# tempSens_Photon.net
KiCad netlist of a schematic drawn in EAGLE
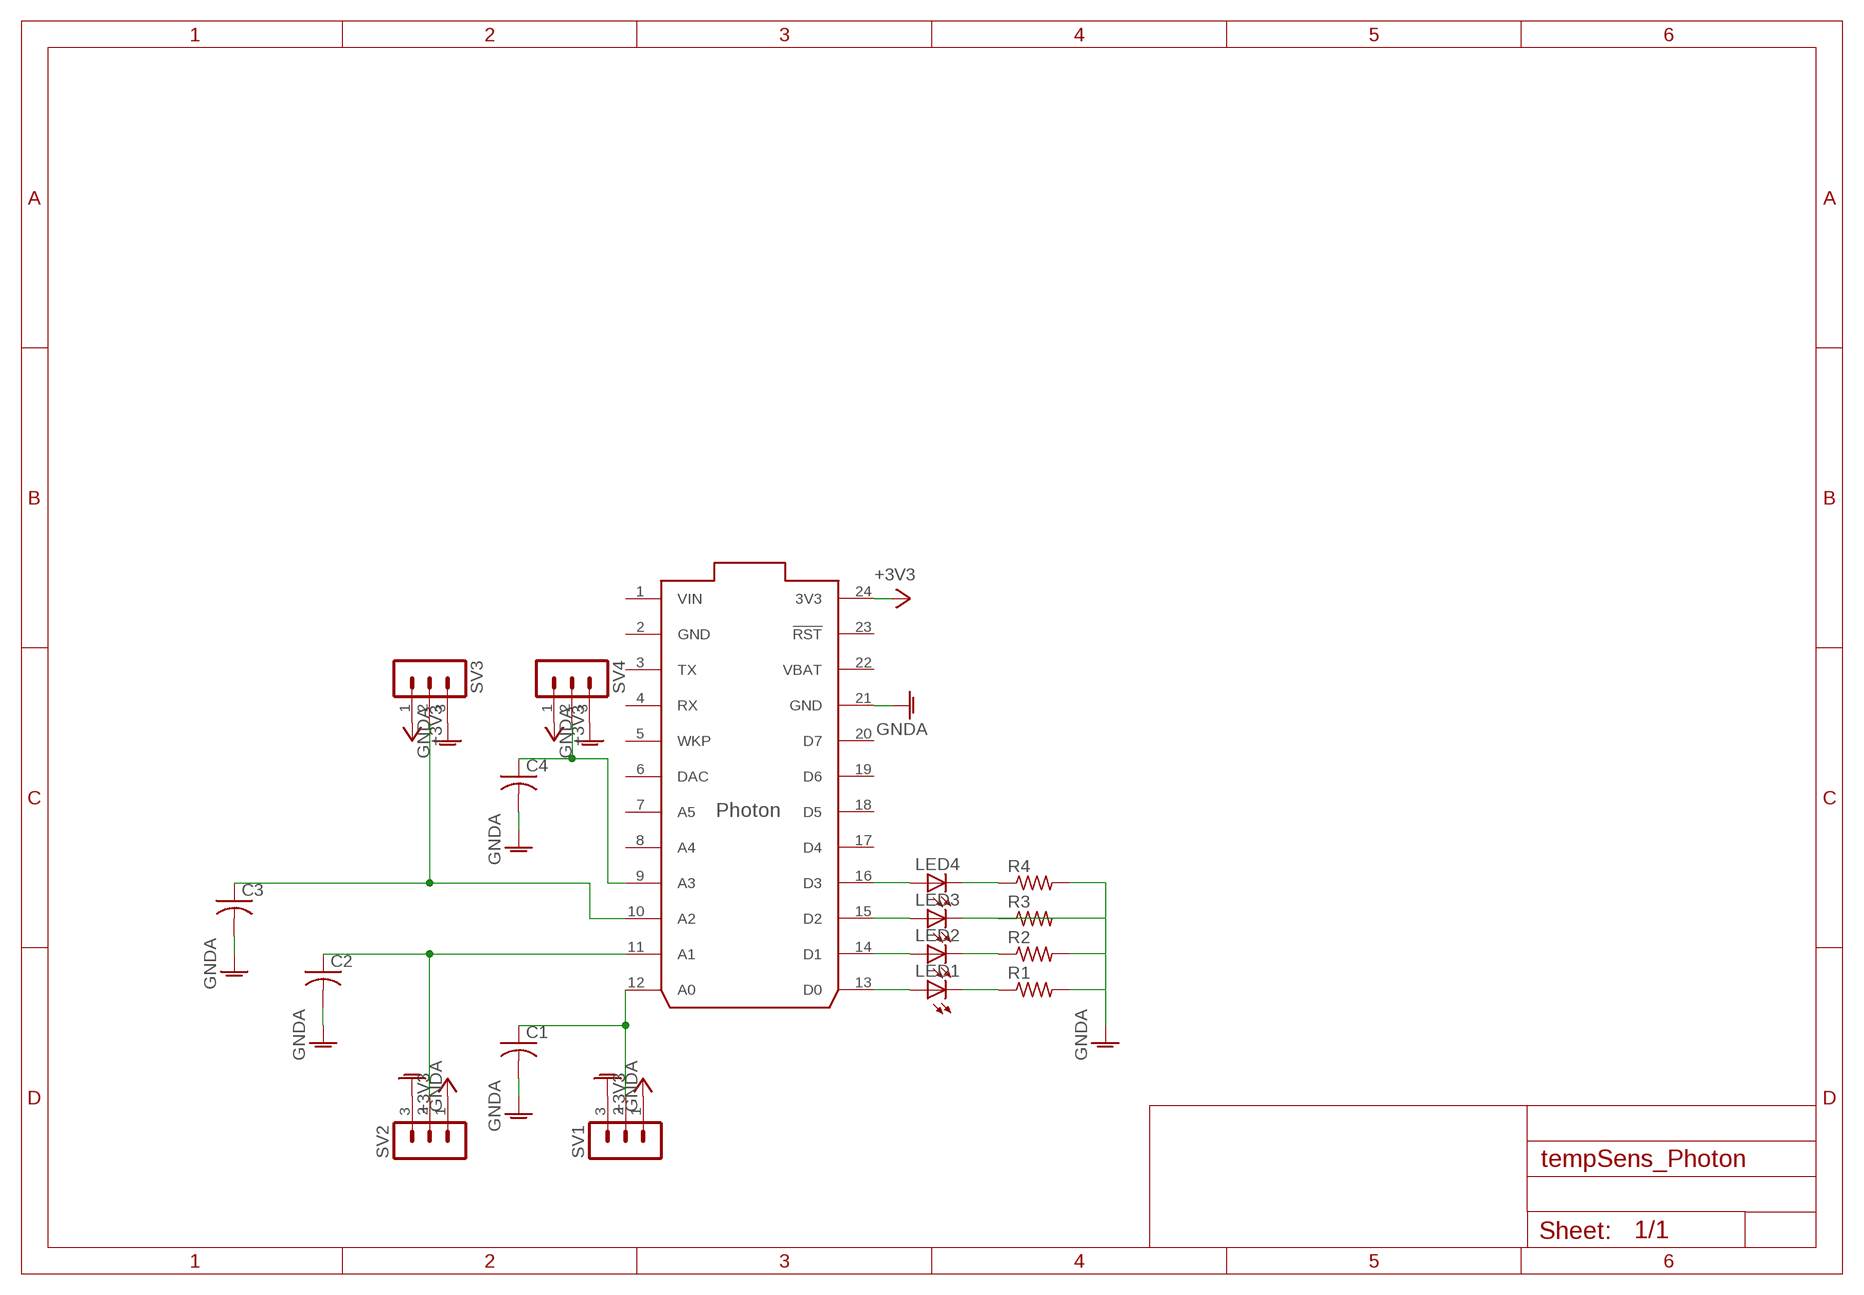
[diagram p0: schematic, sheet 1]

(export (version "E")
  (design (tool "Eeschema 10.0.6"))
  (components
    (comp (ref "C1")
      (value "C-USC0805")
      (footprint "eagle-import:C0805")
      (libsource (lib "eagle-import") (part "C-USC0805"))
    )
    (comp (ref "C2")
      (value "C-USC0805")
      (footprint "eagle-import:C0805")
      (libsource (lib "eagle-import") (part "C-USC0805"))
    )
    (comp (ref "C3")
      (value "C-USC0805")
      (footprint "eagle-import:C0805")
      (libsource (lib "eagle-import") (part "C-USC0805"))
    )
    (comp (ref "C4")
      (value "C-USC0805")
      (footprint "eagle-import:C0805")
      (libsource (lib "eagle-import") (part "C-USC0805"))
    )
    (comp (ref "LED1")
      (value "LEDCHIPLED_0805")
      (footprint "eagle-import:CHIPLED_0805")
      (libsource (lib "eagle-import") (part "LEDCHIPLED_0805"))
    )
    (comp (ref "LED2")
      (value "LEDCHIPLED_0805")
      (footprint "eagle-import:CHIPLED_0805")
      (libsource (lib "eagle-import") (part "LEDCHIPLED_0805"))
    )
    (comp (ref "LED3")
      (value "LEDCHIPLED_0805")
      (footprint "eagle-import:CHIPLED_0805")
      (libsource (lib "eagle-import") (part "LEDCHIPLED_0805"))
    )
    (comp (ref "LED4")
      (value "LEDCHIPLED_0805")
      (footprint "eagle-import:CHIPLED_0805")
      (libsource (lib "eagle-import") (part "LEDCHIPLED_0805"))
    )
    (comp (ref "R1")
      (value "R-US_R0805")
      (footprint "eagle-import:R0805")
      (libsource (lib "eagle-import") (part "R-US_R0805"))
    )
    (comp (ref "R2")
      (value "R-US_R0805")
      (footprint "eagle-import:R0805")
      (libsource (lib "eagle-import") (part "R-US_R0805"))
    )
    (comp (ref "R3")
      (value "R-US_R0805")
      (footprint "eagle-import:R0805")
      (libsource (lib "eagle-import") (part "R-US_R0805"))
    )
    (comp (ref "R4")
      (value "R-US_R0805")
      (footprint "eagle-import:R0805")
      (libsource (lib "eagle-import") (part "R-US_R0805"))
    )
    (comp (ref "SV1")
      (value "CONN3PIN")
      (footprint "eagle-import:MA03-1")
      (libsource (lib "eagle-import") (part "CONN3PIN"))
    )
    (comp (ref "SV2")
      (value "CONN3PIN")
      (footprint "eagle-import:MA03-1")
      (libsource (lib "eagle-import") (part "CONN3PIN"))
    )
    (comp (ref "SV3")
      (value "CONN3PIN")
      (footprint "eagle-import:MA03-1")
      (libsource (lib "eagle-import") (part "CONN3PIN"))
    )
    (comp (ref "SV4")
      (value "CONN3PIN")
      (footprint "eagle-import:MA03-1")
      (libsource (lib "eagle-import") (part "CONN3PIN"))
    )
    (comp (ref "U$1")
      (value "PHOTON_SMD")
      (footprint "eagle-import:PHOTON_SMD")
      (libsource (lib "eagle-import") (part "PHOTON_SMD"))
    )
  )
  (nets
    (net (code "1") (name "+3V3") (class "Default")
      (node (ref "SV1") (pin "1") (pinfunction "1_1") (pintype "passive"))
      (node (ref "SV2") (pin "1") (pinfunction "1_1") (pintype "passive"))
      (node (ref "SV3") (pin "1") (pinfunction "1_1") (pintype "passive"))
      (node (ref "SV4") (pin "1") (pinfunction "1_1") (pintype "passive"))
      (node (ref "U$1") (pin "24") (pinfunction "3V3_24") (pintype "power_in"))
    )
    (net (code "2") (name "/GND") (class "Default")
      (node (ref "U$1") (pin "2") (pinfunction "GND_2") (pintype "power_in"))
    )
    (net (code "3") (name "/VBAT") (class "Default")
      (node (ref "U$1") (pin "22") (pinfunction "VBAT_22") (pintype "power_in"))
    )
    (net (code "4") (name "/VIN") (class "Default")
      (node (ref "U$1") (pin "1") (pinfunction "VIN_1") (pintype "power_in"))
    )
    (net (code "5") (name "GNDA") (class "Default")
      (node (ref "C1") (pin "2") (pinfunction "2_2") (pintype "passive"))
      (node (ref "C2") (pin "2") (pinfunction "2_2") (pintype "passive"))
      (node (ref "C3") (pin "2") (pinfunction "2_2") (pintype "passive"))
      (node (ref "C4") (pin "2") (pinfunction "2_2") (pintype "passive"))
      (node (ref "R1") (pin "2") (pinfunction "2_2") (pintype "passive"))
      (node (ref "R2") (pin "2") (pinfunction "2_2") (pintype "passive"))
      (node (ref "R3") (pin "1") (pinfunction "1_1") (pintype "passive"))
      (node (ref "R4") (pin "2") (pinfunction "2_2") (pintype "passive"))
      (node (ref "SV1") (pin "3") (pinfunction "3_3") (pintype "passive"))
      (node (ref "SV2") (pin "3") (pinfunction "3_3") (pintype "passive"))
      (node (ref "SV3") (pin "3") (pinfunction "3_3") (pintype "passive"))
      (node (ref "SV4") (pin "3") (pinfunction "3_3") (pintype "passive"))
      (node (ref "U$1") (pin "21") (pinfunction "GND_21") (pintype "power_in"))
    )
    (net (code "6") (name "Net-(LED1-PadC)") (class "Default")
      (node (ref "LED1") (pin "C") (pinfunction "C_C") (pintype "passive"))
      (node (ref "R1") (pin "1") (pinfunction "1_1") (pintype "passive"))
    )
    (net (code "7") (name "Net-(LED2-PadC)") (class "Default")
      (node (ref "LED2") (pin "C") (pinfunction "C_C") (pintype "passive"))
      (node (ref "R2") (pin "1") (pinfunction "1_1") (pintype "passive"))
    )
    (net (code "8") (name "Net-(LED3-PadC)") (class "Default")
      (node (ref "LED3") (pin "C") (pinfunction "C_C") (pintype "passive"))
      (node (ref "R3") (pin "2") (pinfunction "2_2") (pintype "passive"))
    )
    (net (code "9") (name "Net-(LED4-PadC)") (class "Default")
      (node (ref "LED4") (pin "C") (pinfunction "C_C") (pintype "passive"))
      (node (ref "R4") (pin "1") (pinfunction "1_1") (pintype "passive"))
    )
    (net (code "10") (name "Net-(U$1A-A0)") (class "Default")
      (node (ref "C1") (pin "1") (pinfunction "1_1") (pintype "passive"))
      (node (ref "SV1") (pin "2") (pinfunction "2_2") (pintype "passive"))
      (node (ref "U$1") (pin "12") (pinfunction "A0_12") (pintype "bidirectional"))
    )
    (net (code "11") (name "Net-(U$1A-A1)") (class "Default")
      (node (ref "C2") (pin "1") (pinfunction "1_1") (pintype "passive"))
      (node (ref "SV2") (pin "2") (pinfunction "2_2") (pintype "passive"))
      (node (ref "U$1") (pin "11") (pinfunction "A1_11") (pintype "bidirectional"))
    )
    (net (code "12") (name "Net-(U$1A-A2)") (class "Default")
      (node (ref "C3") (pin "1") (pinfunction "1_1") (pintype "passive"))
      (node (ref "SV3") (pin "2") (pinfunction "2_2") (pintype "passive"))
      (node (ref "U$1") (pin "10") (pinfunction "A2_10") (pintype "bidirectional"))
    )
    (net (code "13") (name "Net-(U$1A-A3)") (class "Default")
      (node (ref "C4") (pin "1") (pinfunction "1_1") (pintype "passive"))
      (node (ref "SV4") (pin "2") (pinfunction "2_2") (pintype "passive"))
      (node (ref "U$1") (pin "9") (pinfunction "A3_9") (pintype "bidirectional"))
    )
    (net (code "14") (name "Net-(U$1A-D0)") (class "Default")
      (node (ref "LED1") (pin "A") (pinfunction "A_A") (pintype "passive"))
      (node (ref "U$1") (pin "13") (pinfunction "D0_13") (pintype "bidirectional"))
    )
    (net (code "15") (name "Net-(U$1A-D1)") (class "Default")
      (node (ref "LED2") (pin "A") (pinfunction "A_A") (pintype "passive"))
      (node (ref "U$1") (pin "14") (pinfunction "D1_14") (pintype "bidirectional"))
    )
    (net (code "16") (name "Net-(U$1A-D2)") (class "Default")
      (node (ref "LED3") (pin "A") (pinfunction "A_A") (pintype "passive"))
      (node (ref "U$1") (pin "15") (pinfunction "D2_15") (pintype "bidirectional"))
    )
    (net (code "17") (name "Net-(U$1A-D3)") (class "Default")
      (node (ref "LED4") (pin "A") (pinfunction "A_A") (pintype "passive"))
      (node (ref "U$1") (pin "16") (pinfunction "D3_16") (pintype "bidirectional"))
    )
    (net (code "18") (name "unconnected-(U$1A-A4-Pad8)") (class "Default")
      (node (ref "U$1") (pin "8") (pinfunction "A4_8") (pintype "bidirectional"))
    )
    (net (code "19") (name "unconnected-(U$1A-A5-Pad7)") (class "Default")
      (node (ref "U$1") (pin "7") (pinfunction "A5_7") (pintype "bidirectional"))
    )
    (net (code "20") (name "unconnected-(U$1A-D4-Pad17)") (class "Default")
      (node (ref "U$1") (pin "17") (pinfunction "D4_17") (pintype "bidirectional"))
    )
    (net (code "21") (name "unconnected-(U$1A-D5-Pad18)") (class "Default")
      (node (ref "U$1") (pin "18") (pinfunction "D5_18") (pintype "bidirectional"))
    )
    (net (code "22") (name "unconnected-(U$1A-D6-Pad19)") (class "Default")
      (node (ref "U$1") (pin "19") (pinfunction "D6_19") (pintype "bidirectional"))
    )
    (net (code "23") (name "unconnected-(U$1A-D7-Pad20)") (class "Default")
      (node (ref "U$1") (pin "20") (pinfunction "D7_20") (pintype "bidirectional"))
    )
    (net (code "24") (name "unconnected-(U$1A-DAC-Pad6)") (class "Default")
      (node (ref "U$1") (pin "6") (pinfunction "DAC_6") (pintype "bidirectional"))
    )
    (net (code "25") (name "unconnected-(U$1A-RX-Pad4)") (class "Default")
      (node (ref "U$1") (pin "4") (pinfunction "RX_4") (pintype "bidirectional"))
    )
    (net (code "26") (name "unconnected-(U$1A-TX-Pad3)") (class "Default")
      (node (ref "U$1") (pin "3") (pinfunction "TX_3") (pintype "bidirectional"))
    )
    (net (code "27") (name "unconnected-(U$1A-WKP-Pad5)") (class "Default")
      (node (ref "U$1") (pin "5") (pinfunction "WKP_5") (pintype "bidirectional"))
    )
    (net (code "28") (name "unconnected-(U$1A-~{RST}-Pad23)") (class "Default")
      (node (ref "U$1") (pin "23") (pinfunction "~{RST}_23") (pintype "bidirectional"))
    )
  )
)
